# FPGA_power.net
KiCad netlist of a schematic drawn in Altium Designer
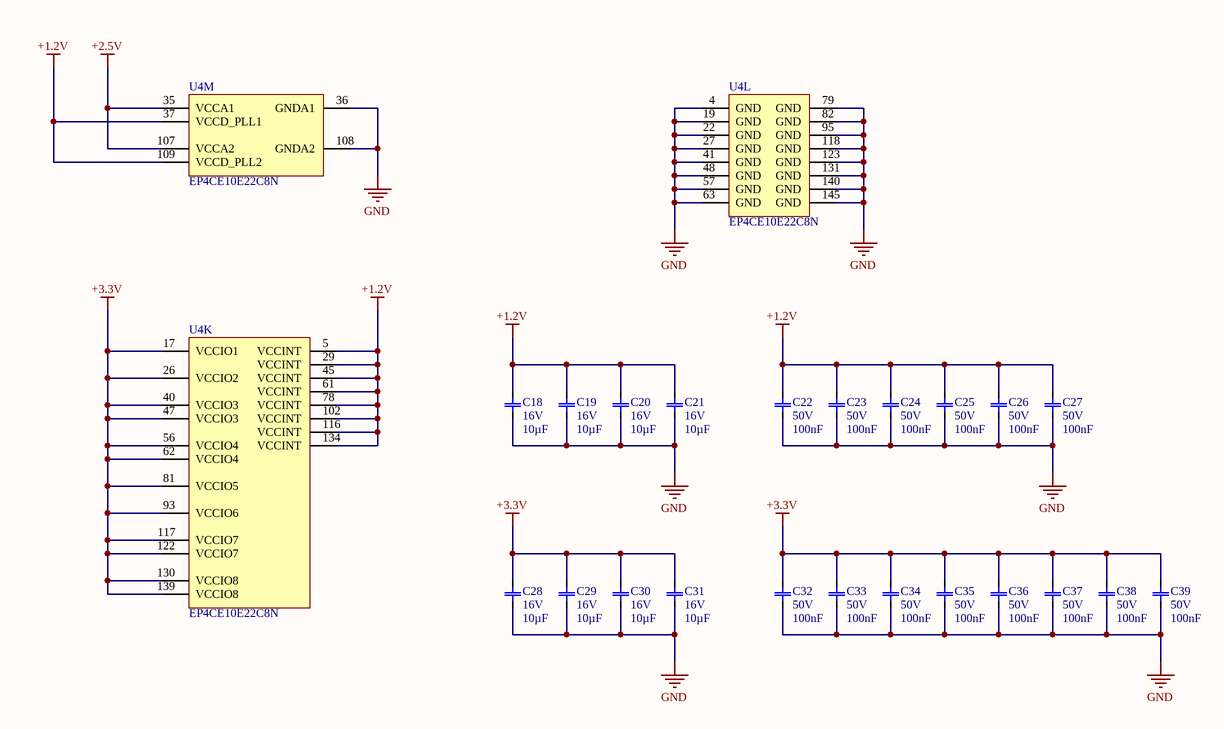
[diagram p0: FPGA_power.SchDoc]

(export (version "E")
  (design (tool "Eeschema 10.0.6"))
  (components
    (comp (ref "C18")
      (value "10µF")
      (footprint "MLCC_1210")
      (description "MLCC 10µF 16V 1210")
      (fields (field (name "VOLTAGE") "16V"))
      (libsource (lib "Nixie") (part "MLCC 10µF 16V 1210"))
    )
    (comp (ref "C19")
      (value "10µF")
      (footprint "MLCC_1210")
      (description "MLCC 10µF 16V 1210")
      (fields (field (name "VOLTAGE") "16V"))
      (libsource (lib "Nixie") (part "MLCC 10µF 16V 1210"))
    )
    (comp (ref "C20")
      (value "10µF")
      (footprint "MLCC_1210")
      (description "MLCC 10µF 16V 1210")
      (fields (field (name "VOLTAGE") "16V"))
      (libsource (lib "Nixie") (part "MLCC 10µF 16V 1210"))
    )
    (comp (ref "C21")
      (value "10µF")
      (footprint "MLCC_1210")
      (description "MLCC 10µF 16V 1210")
      (fields (field (name "VOLTAGE") "16V"))
      (libsource (lib "Nixie") (part "MLCC 10µF 16V 1210"))
    )
    (comp (ref "C22")
      (value "100nF")
      (footprint "MLCC_0603")
      (description "MLCC 100nF 50V 0603")
      (fields (field (name "VOLTAGE") "50V"))
      (libsource (lib "Nixie") (part "MLCC 100nF 50V 0603"))
    )
    (comp (ref "C23")
      (value "100nF")
      (footprint "MLCC_0603")
      (description "MLCC 100nF 50V 0603")
      (fields (field (name "VOLTAGE") "50V"))
      (libsource (lib "Nixie") (part "MLCC 100nF 50V 0603"))
    )
    (comp (ref "C24")
      (value "100nF")
      (footprint "MLCC_0603")
      (description "MLCC 100nF 50V 0603")
      (fields (field (name "VOLTAGE") "50V"))
      (libsource (lib "Nixie") (part "MLCC 100nF 50V 0603"))
    )
    (comp (ref "C25")
      (value "100nF")
      (footprint "MLCC_0603")
      (description "MLCC 100nF 50V 0603")
      (fields (field (name "VOLTAGE") "50V"))
      (libsource (lib "Nixie") (part "MLCC 100nF 50V 0603"))
    )
    (comp (ref "C26")
      (value "100nF")
      (footprint "MLCC_0603")
      (description "MLCC 100nF 50V 0603")
      (fields (field (name "VOLTAGE") "50V"))
      (libsource (lib "Nixie") (part "MLCC 100nF 50V 0603"))
    )
    (comp (ref "C27")
      (value "100nF")
      (footprint "MLCC_0603")
      (description "MLCC 100nF 50V 0603")
      (fields (field (name "VOLTAGE") "50V"))
      (libsource (lib "Nixie") (part "MLCC 100nF 50V 0603"))
    )
    (comp (ref "C28")
      (value "10µF")
      (footprint "MLCC_1210")
      (description "MLCC 10µF 16V 1210")
      (fields (field (name "VOLTAGE") "16V"))
      (libsource (lib "Nixie") (part "MLCC 10µF 16V 1210"))
    )
    (comp (ref "C29")
      (value "10µF")
      (footprint "MLCC_1210")
      (description "MLCC 10µF 16V 1210")
      (fields (field (name "VOLTAGE") "16V"))
      (libsource (lib "Nixie") (part "MLCC 10µF 16V 1210"))
    )
    (comp (ref "C30")
      (value "10µF")
      (footprint "MLCC_1210")
      (description "MLCC 10µF 16V 1210")
      (fields (field (name "VOLTAGE") "16V"))
      (libsource (lib "Nixie") (part "MLCC 10µF 16V 1210"))
    )
    (comp (ref "C31")
      (value "10µF")
      (footprint "MLCC_1210")
      (description "MLCC 10µF 16V 1210")
      (fields (field (name "VOLTAGE") "16V"))
      (libsource (lib "Nixie") (part "MLCC 10µF 16V 1210"))
    )
    (comp (ref "C32")
      (value "100nF")
      (footprint "MLCC_0603")
      (description "MLCC 100nF 50V 0603")
      (fields (field (name "VOLTAGE") "50V"))
      (libsource (lib "Nixie") (part "MLCC 100nF 50V 0603"))
    )
    (comp (ref "C33")
      (value "100nF")
      (footprint "MLCC_0603")
      (description "MLCC 100nF 50V 0603")
      (fields (field (name "VOLTAGE") "50V"))
      (libsource (lib "Nixie") (part "MLCC 100nF 50V 0603"))
    )
    (comp (ref "C34")
      (value "100nF")
      (footprint "MLCC_0603")
      (description "MLCC 100nF 50V 0603")
      (fields (field (name "VOLTAGE") "50V"))
      (libsource (lib "Nixie") (part "MLCC 100nF 50V 0603"))
    )
    (comp (ref "C35")
      (value "100nF")
      (footprint "MLCC_0603")
      (description "MLCC 100nF 50V 0603")
      (fields (field (name "VOLTAGE") "50V"))
      (libsource (lib "Nixie") (part "MLCC 100nF 50V 0603"))
    )
    (comp (ref "C36")
      (value "100nF")
      (footprint "MLCC_0603")
      (description "MLCC 100nF 50V 0603")
      (fields (field (name "VOLTAGE") "50V"))
      (libsource (lib "Nixie") (part "MLCC 100nF 50V 0603"))
    )
    (comp (ref "C37")
      (value "100nF")
      (footprint "MLCC_0603")
      (description "MLCC 100nF 50V 0603")
      (fields (field (name "VOLTAGE") "50V"))
      (libsource (lib "Nixie") (part "MLCC 100nF 50V 0603"))
    )
    (comp (ref "C38")
      (value "100nF")
      (footprint "MLCC_0603")
      (description "MLCC 100nF 50V 0603")
      (fields (field (name "VOLTAGE") "50V"))
      (libsource (lib "Nixie") (part "MLCC 100nF 50V 0603"))
    )
    (comp (ref "C39")
      (value "100nF")
      (footprint "MLCC_0603")
      (description "MLCC 100nF 50V 0603")
      (fields (field (name "VOLTAGE") "50V"))
      (libsource (lib "Nixie") (part "MLCC 100nF 50V 0603"))
    )
    (comp (ref "U4")
      (value "EP4CE10E22C8N")
      (footprint "EP4CE10E22C8N")
      (fields (field (name "MANUFACTURER") "Altera"))
      (libsource (lib "Nixie") (part "EP4CE10E22C8N"))
    )
  )
  (nets
    (net (code "1") (name "+1.2V") (class "Default")
      (node (ref "C18") (pin "2") (pinfunction "2_2") (pintype "passive"))
      (node (ref "C19") (pin "2") (pinfunction "2_2") (pintype "passive"))
      (node (ref "C20") (pin "2") (pinfunction "2_2") (pintype "passive"))
      (node (ref "C21") (pin "2") (pinfunction "2_2") (pintype "passive"))
      (node (ref "C22") (pin "2") (pinfunction "2_2") (pintype "passive"))
      (node (ref "C23") (pin "2") (pinfunction "2_2") (pintype "passive"))
      (node (ref "C24") (pin "2") (pinfunction "2_2") (pintype "passive"))
      (node (ref "C25") (pin "2") (pinfunction "2_2") (pintype "passive"))
      (node (ref "C26") (pin "2") (pinfunction "2_2") (pintype "passive"))
      (node (ref "C27") (pin "2") (pinfunction "2_2") (pintype "passive"))
      (node (ref "U4") (pin "102") (pinfunction "VCCINT_102") (pintype "power_in"))
      (node (ref "U4") (pin "109") (pinfunction "VCCD_PLL2_109") (pintype "power_in"))
      (node (ref "U4") (pin "116") (pinfunction "VCCINT_116") (pintype "power_in"))
      (node (ref "U4") (pin "134") (pinfunction "VCCINT_134") (pintype "power_in"))
      (node (ref "U4") (pin "29") (pinfunction "VCCINT_29") (pintype "power_in"))
      (node (ref "U4") (pin "37") (pinfunction "VCCD_PLL1_37") (pintype "power_in"))
      (node (ref "U4") (pin "45") (pinfunction "VCCINT_45") (pintype "power_in"))
      (node (ref "U4") (pin "5") (pinfunction "VCCINT_5") (pintype "power_in"))
      (node (ref "U4") (pin "61") (pinfunction "VCCINT_61") (pintype "power_in"))
      (node (ref "U4") (pin "78") (pinfunction "VCCINT_78") (pintype "power_in"))
    )
    (net (code "2") (name "+2.5V") (class "Default")
      (node (ref "U4") (pin "107") (pinfunction "VCCA2_107") (pintype "power_in"))
      (node (ref "U4") (pin "35") (pinfunction "VCCA1_35") (pintype "power_in"))
    )
    (net (code "3") (name "+3.3V") (class "Default")
      (node (ref "C28") (pin "2") (pinfunction "2_2") (pintype "passive"))
      (node (ref "C29") (pin "2") (pinfunction "2_2") (pintype "passive"))
      (node (ref "C30") (pin "2") (pinfunction "2_2") (pintype "passive"))
      (node (ref "C31") (pin "2") (pinfunction "2_2") (pintype "passive"))
      (node (ref "C32") (pin "2") (pinfunction "2_2") (pintype "passive"))
      (node (ref "C33") (pin "2") (pinfunction "2_2") (pintype "passive"))
      (node (ref "C34") (pin "2") (pinfunction "2_2") (pintype "passive"))
      (node (ref "C35") (pin "2") (pinfunction "2_2") (pintype "passive"))
      (node (ref "C36") (pin "2") (pinfunction "2_2") (pintype "passive"))
      (node (ref "C37") (pin "2") (pinfunction "2_2") (pintype "passive"))
      (node (ref "C38") (pin "2") (pinfunction "2_2") (pintype "passive"))
      (node (ref "C39") (pin "2") (pinfunction "2_2") (pintype "passive"))
      (node (ref "U4") (pin "117") (pinfunction "VCCIO7_117") (pintype "power_in"))
      (node (ref "U4") (pin "122") (pinfunction "VCCIO7_122") (pintype "power_in"))
      (node (ref "U4") (pin "130") (pinfunction "VCCIO8_130") (pintype "power_in"))
      (node (ref "U4") (pin "139") (pinfunction "VCCIO8_139") (pintype "power_in"))
      (node (ref "U4") (pin "17") (pinfunction "VCCIO1_17") (pintype "power_in"))
      (node (ref "U4") (pin "26") (pinfunction "VCCIO2_26") (pintype "power_in"))
      (node (ref "U4") (pin "40") (pinfunction "VCCIO3_40") (pintype "power_in"))
      (node (ref "U4") (pin "47") (pinfunction "VCCIO3_47") (pintype "power_in"))
      (node (ref "U4") (pin "56") (pinfunction "VCCIO4_56") (pintype "power_in"))
      (node (ref "U4") (pin "62") (pinfunction "VCCIO4_62") (pintype "power_in"))
      (node (ref "U4") (pin "81") (pinfunction "VCCIO5_81") (pintype "power_in"))
      (node (ref "U4") (pin "93") (pinfunction "VCCIO6_93") (pintype "power_in"))
    )
    (net (code "4") (name "GND") (class "Default")
      (node (ref "C18") (pin "1") (pinfunction "1_1") (pintype "passive"))
      (node (ref "C19") (pin "1") (pinfunction "1_1") (pintype "passive"))
      (node (ref "C20") (pin "1") (pinfunction "1_1") (pintype "passive"))
      (node (ref "C21") (pin "1") (pinfunction "1_1") (pintype "passive"))
      (node (ref "C22") (pin "1") (pinfunction "1_1") (pintype "passive"))
      (node (ref "C23") (pin "1") (pinfunction "1_1") (pintype "passive"))
      (node (ref "C24") (pin "1") (pinfunction "1_1") (pintype "passive"))
      (node (ref "C25") (pin "1") (pinfunction "1_1") (pintype "passive"))
      (node (ref "C26") (pin "1") (pinfunction "1_1") (pintype "passive"))
      (node (ref "C27") (pin "1") (pinfunction "1_1") (pintype "passive"))
      (node (ref "C28") (pin "1") (pinfunction "1_1") (pintype "passive"))
      (node (ref "C29") (pin "1") (pinfunction "1_1") (pintype "passive"))
      (node (ref "C30") (pin "1") (pinfunction "1_1") (pintype "passive"))
      (node (ref "C31") (pin "1") (pinfunction "1_1") (pintype "passive"))
      (node (ref "C32") (pin "1") (pinfunction "1_1") (pintype "passive"))
      (node (ref "C33") (pin "1") (pinfunction "1_1") (pintype "passive"))
      (node (ref "C34") (pin "1") (pinfunction "1_1") (pintype "passive"))
      (node (ref "C35") (pin "1") (pinfunction "1_1") (pintype "passive"))
      (node (ref "C36") (pin "1") (pinfunction "1_1") (pintype "passive"))
      (node (ref "C37") (pin "1") (pinfunction "1_1") (pintype "passive"))
      (node (ref "C38") (pin "1") (pinfunction "1_1") (pintype "passive"))
      (node (ref "C39") (pin "1") (pinfunction "1_1") (pintype "passive"))
      (node (ref "U4") (pin "108") (pinfunction "GNDA2_108") (pintype "power_in"))
      (node (ref "U4") (pin "118") (pinfunction "GND_118") (pintype "power_in"))
      (node (ref "U4") (pin "123") (pinfunction "GND_123") (pintype "power_in"))
      (node (ref "U4") (pin "131") (pinfunction "GND_131") (pintype "power_in"))
      (node (ref "U4") (pin "140") (pinfunction "GND_140") (pintype "power_in"))
      (node (ref "U4") (pin "145") (pinfunction "GND_145") (pintype "power_in"))
      (node (ref "U4") (pin "19") (pinfunction "GND_19") (pintype "power_in"))
      (node (ref "U4") (pin "22") (pinfunction "GND_22") (pintype "power_in"))
      (node (ref "U4") (pin "27") (pinfunction "GND_27") (pintype "power_in"))
      (node (ref "U4") (pin "36") (pinfunction "GNDA1_36") (pintype "power_in"))
      (node (ref "U4") (pin "4") (pinfunction "GND_4") (pintype "power_in"))
      (node (ref "U4") (pin "41") (pinfunction "GND_41") (pintype "power_in"))
      (node (ref "U4") (pin "48") (pinfunction "GND_48") (pintype "power_in"))
      (node (ref "U4") (pin "57") (pinfunction "GND_57") (pintype "power_in"))
      (node (ref "U4") (pin "63") (pinfunction "GND_63") (pintype "power_in"))
      (node (ref "U4") (pin "79") (pinfunction "GND_79") (pintype "power_in"))
      (node (ref "U4") (pin "82") (pinfunction "GND_82") (pintype "power_in"))
      (node (ref "U4") (pin "95") (pinfunction "GND_95") (pintype "power_in"))
    )
  )
)
